# Main.net
KiCad netlist of a schematic drawn in Altium Designer
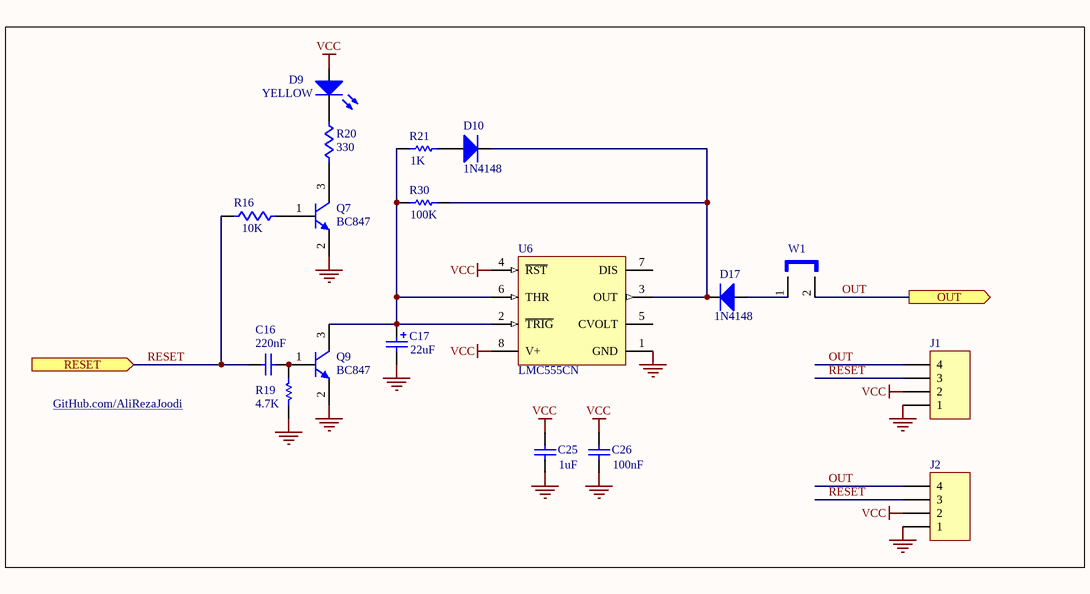
[diagram p0: Main.SchDoc]

(export (version "E")
  (design (tool "Eeschema 10.0.6"))
  (components
    (comp (ref "C16")
      (value "220nF")
      (footprint "RESC3216N")
      (description "Capacitor")
      (fields (field (name "PUBLISHER") "Altium Limited"))
      (libsource (lib "Miscellaneous Devices") (part "Cap"))
    )
    (comp (ref "C17")
      (value "22uF")
      (footprint "Cap_B")
      (description "Polarized Capacitor (Radial)")
      (fields (field (name "MANUFACTURER") "Generic Components") (field (name "PUBLISHER") "Altium Limited"))
      (libsource (lib "Miscellaneous Devices") (part "Cap Pol1"))
    )
    (comp (ref "C25")
      (value "1uF")
      (footprint "0805")
      (description "Capacitor")
      (fields (field (name "MANUFACTURER") "Generic Components") (field (name "PUBLISHER") "Altium Limited"))
      (libsource (lib "Miscellaneous Devices") (part "Cap"))
    )
    (comp (ref "C26")
      (value "100nF")
      (footprint "0805")
      (description "Capacitor")
      (fields (field (name "MANUFACTURER") "Generic Components") (field (name "PUBLISHER") "Altium Limited"))
      (libsource (lib "Miscellaneous Devices") (part "Cap"))
    )
    (comp (ref "D9")
      (value "YELLOW")
      (footprint "0805_Diode")
      (description "Typical INFRARED GaAs LED")
      (fields (field (name "MANUFACTURER") "Generic Components") (field (name "PUBLISHER") "Altium Limited"))
      (libsource (lib "Miscellaneous Devices") (part "LED"))
    )
    (comp (ref "D10")
      (value "1N4148")
      (footprint "0805_Diode")
      (description "Default Diode")
      (fields
        (field (name "MANUFACTURER") "Generic Components")
        (field (name "Comment") "Diode")
        (field (name "PUBLISHER") "Altium Limited")
      )
      (libsource (lib "Miscellaneous Devices") (part "Diode"))
    )
    (comp (ref "D17")
      (value "1N4148")
      (footprint "0805_Diode")
      (description "Default Diode")
      (fields (field (name "MANUFACTURER") "Generic Components") (field (name "PUBLISHER") "Altium Limited"))
      (libsource (lib "Miscellaneous Devices") (part "Diode"))
    )
    (comp (ref "J1")
      (value "4PIN")
      (footprint "HDR1X4")
      (description "Header, 4-Pin")
      (fields (field (name "MANUFACTURER") "Generic Components") (field (name "PUBLISHER") "Altium Limited"))
      (libsource (lib "Miscellaneous Connectors") (part "Header 4"))
    )
    (comp (ref "J2")
      (value "4PIN")
      (footprint "HDR1X4")
      (description "Header, 4-Pin")
      (fields (field (name "MANUFACTURER") "Generic Components") (field (name "PUBLISHER") "Altium Limited"))
      (libsource (lib "Miscellaneous Connectors") (part "Header 4"))
    )
    (comp (ref "Q7")
      (value "BC847")
      (footprint "SOT23-3N")
      (description "Silicon Bipolar Transistor")
      (fields (field (name "Comment") "NPN"))
      (libsource (lib "my Libraries") (part "BC847"))
    )
    (comp (ref "Q9")
      (value "BC847")
      (footprint "SOT23-3N")
      (description "Silicon Bipolar Transistor")
      (libsource (lib "my Libraries") (part "BC847"))
    )
    (comp (ref "R16")
      (value "10K")
      (footprint "0805")
      (description "Resistor")
      (fields (field (name "MANUFACTURER") "Generic Components") (field (name "PUBLISHER") "Altium Limited"))
      (libsource (lib "") (part "Res1_1"))
    )
    (comp (ref "R19")
      (value "4.7K")
      (footprint "0805")
      (description "Resistor")
      (fields (field (name "PUBLISHER") "Altium Limited"))
      (libsource (lib "Miscellaneous Devices") (part "Res1"))
    )
    (comp (ref "R20")
      (value "330")
      (footprint "0805")
      (description "Resistor")
      (fields (field (name "MANUFACTURER") "Generic Components") (field (name "PUBLISHER") "Altium Limited"))
      (libsource (lib "") (part "Res1_1"))
    )
    (comp (ref "R21")
      (value "1K")
      (footprint "0805")
      (description "Resistor")
      (fields (field (name "PUBLISHER") "Altium Limited"))
      (libsource (lib "Miscellaneous Devices") (part "Res1"))
    )
    (comp (ref "R30")
      (value "100K")
      (footprint "0805")
      (description "Resistor")
      (fields (field (name "PUBLISHER") "Altium Limited"))
      (libsource (lib "Miscellaneous Devices") (part "Res1"))
    )
    (comp (ref "U6")
      (value "LMC555CN")
      (footprint "SOP127P636-8N")
      (description "CMOS Timer, 8-pin MDIP")
      (fields
        (field (name "MANUFACTURER") "National Semiconductor")
        (field (name "PUBLISHER") "Altium Limited")
      )
      (libsource (lib "NSC Analog") (part "LMC555CN"))
    )
    (comp (ref "W1")
      (value "Jumper 2pin")
      (footprint "Jumper_SMD")
      (description "Jumper Wire")
      (fields (field (name "MANUFACTURER") "Generic Components") (field (name "PUBLISHER") "Altium Limited"))
      (libsource (lib "my Libraries") (part "Jumper 2pin"))
    )
  )
  (nets
    (net (code "1") (name "/OUT") (class "Default")
      (node (ref "J1") (pin "4") (pinfunction "4_4") (pintype "passive"))
      (node (ref "J2") (pin "4") (pinfunction "4_4") (pintype "passive"))
      (node (ref "W1") (pin "2") (pinfunction "2_2") (pintype "passive"))
    )
    (net (code "2") (name "/RESET") (class "Default")
      (node (ref "C16") (pin "1") (pinfunction "1_1") (pintype "passive"))
      (node (ref "J1") (pin "3") (pinfunction "3_3") (pintype "passive"))
      (node (ref "J2") (pin "3") (pinfunction "3_3") (pintype "passive"))
      (node (ref "R16") (pin "1") (pinfunction "1_1") (pintype "passive"))
    )
    (net (code "3") (name "GND") (class "Default")
      (node (ref "C17") (pin "2") (pinfunction "2_2") (pintype "passive"))
      (node (ref "C25") (pin "1") (pinfunction "1_1") (pintype "passive"))
      (node (ref "C26") (pin "1") (pinfunction "1_1") (pintype "passive"))
      (node (ref "J1") (pin "1") (pinfunction "1_1") (pintype "passive"))
      (node (ref "J2") (pin "1") (pinfunction "1_1") (pintype "passive"))
      (node (ref "Q7") (pin "2") (pinfunction "E_2") (pintype "passive"))
      (node (ref "Q9") (pin "2") (pinfunction "E_2") (pintype "passive"))
      (node (ref "R19") (pin "2") (pinfunction "2_2") (pintype "passive"))
      (node (ref "U6") (pin "1") (pinfunction "GND_1") (pintype "power_in"))
    )
    (net (code "4") (name "Net-(D9-K)") (class "Default")
      (node (ref "D9") (pin "2") (pinfunction "K_2") (pintype "passive"))
      (node (ref "R20") (pin "1") (pinfunction "1_1") (pintype "passive"))
    )
    (net (code "5") (name "Net-(D10-A)") (class "Default")
      (node (ref "D10") (pin "1") (pinfunction "A_1") (pintype "passive"))
      (node (ref "R21") (pin "2") (pinfunction "2_2") (pintype "passive"))
    )
    (net (code "6") (name "Net-(D10-K)") (class "Default")
      (node (ref "D10") (pin "2") (pinfunction "K_2") (pintype "passive"))
      (node (ref "D17") (pin "2") (pinfunction "K_2") (pintype "passive"))
      (node (ref "R30") (pin "2") (pinfunction "2_2") (pintype "passive"))
      (node (ref "U6") (pin "3") (pinfunction "OUT_3") (pintype "output"))
    )
    (net (code "7") (name "Net-(D17-A)") (class "Default")
      (node (ref "D17") (pin "1") (pinfunction "A_1") (pintype "passive"))
      (node (ref "W1") (pin "1") (pinfunction "1_1") (pintype "passive"))
    )
    (net (code "8") (name "Net-(Q7-B)") (class "Default")
      (node (ref "Q7") (pin "1") (pinfunction "B_1") (pintype "passive"))
      (node (ref "R16") (pin "2") (pinfunction "2_2") (pintype "passive"))
    )
    (net (code "9") (name "Net-(Q7-C)") (class "Default")
      (node (ref "Q7") (pin "3") (pinfunction "C_3") (pintype "passive"))
      (node (ref "R20") (pin "2") (pinfunction "2_2") (pintype "passive"))
    )
    (net (code "10") (name "Net-(Q9-B)") (class "Default")
      (node (ref "C16") (pin "2") (pinfunction "2_2") (pintype "passive"))
      (node (ref "Q9") (pin "1") (pinfunction "B_1") (pintype "passive"))
      (node (ref "R19") (pin "1") (pinfunction "1_1") (pintype "passive"))
    )
    (net (code "11") (name "Net-(Q9-C)") (class "Default")
      (node (ref "C17") (pin "1") (pinfunction "1_1") (pintype "passive"))
      (node (ref "Q9") (pin "3") (pinfunction "C_3") (pintype "passive"))
      (node (ref "R21") (pin "1") (pinfunction "1_1") (pintype "passive"))
      (node (ref "R30") (pin "1") (pinfunction "1_1") (pintype "passive"))
      (node (ref "U6") (pin "2") (pinfunction "~{TRIG}_2") (pintype "input"))
      (node (ref "U6") (pin "6") (pinfunction "THR_6") (pintype "input"))
    )
    (net (code "12") (name "VCC") (class "Default")
      (node (ref "C25") (pin "2") (pinfunction "2_2") (pintype "passive"))
      (node (ref "C26") (pin "2") (pinfunction "2_2") (pintype "passive"))
      (node (ref "D9") (pin "1") (pinfunction "A_1") (pintype "passive"))
      (node (ref "J1") (pin "2") (pinfunction "2_2") (pintype "passive"))
      (node (ref "J2") (pin "2") (pinfunction "2_2") (pintype "passive"))
      (node (ref "U6") (pin "4") (pinfunction "~{RST}_4") (pintype "input"))
      (node (ref "U6") (pin "8") (pinfunction "V+_8") (pintype "power_in"))
    )
    (net (code "13") (name "unconnected-(U6-CVOLT-Pad5)") (class "Default")
      (node (ref "U6") (pin "5") (pinfunction "CVOLT_5") (pintype "passive"))
    )
    (net (code "14") (name "unconnected-(U6-DIS-Pad7)") (class "Default")
      (node (ref "U6") (pin "7") (pinfunction "DIS_7") (pintype "open_collector"))
    )
  )
)
